# MoteWatch_Vers_2.net
KiCad netlist of a schematic drawn in EAGLE
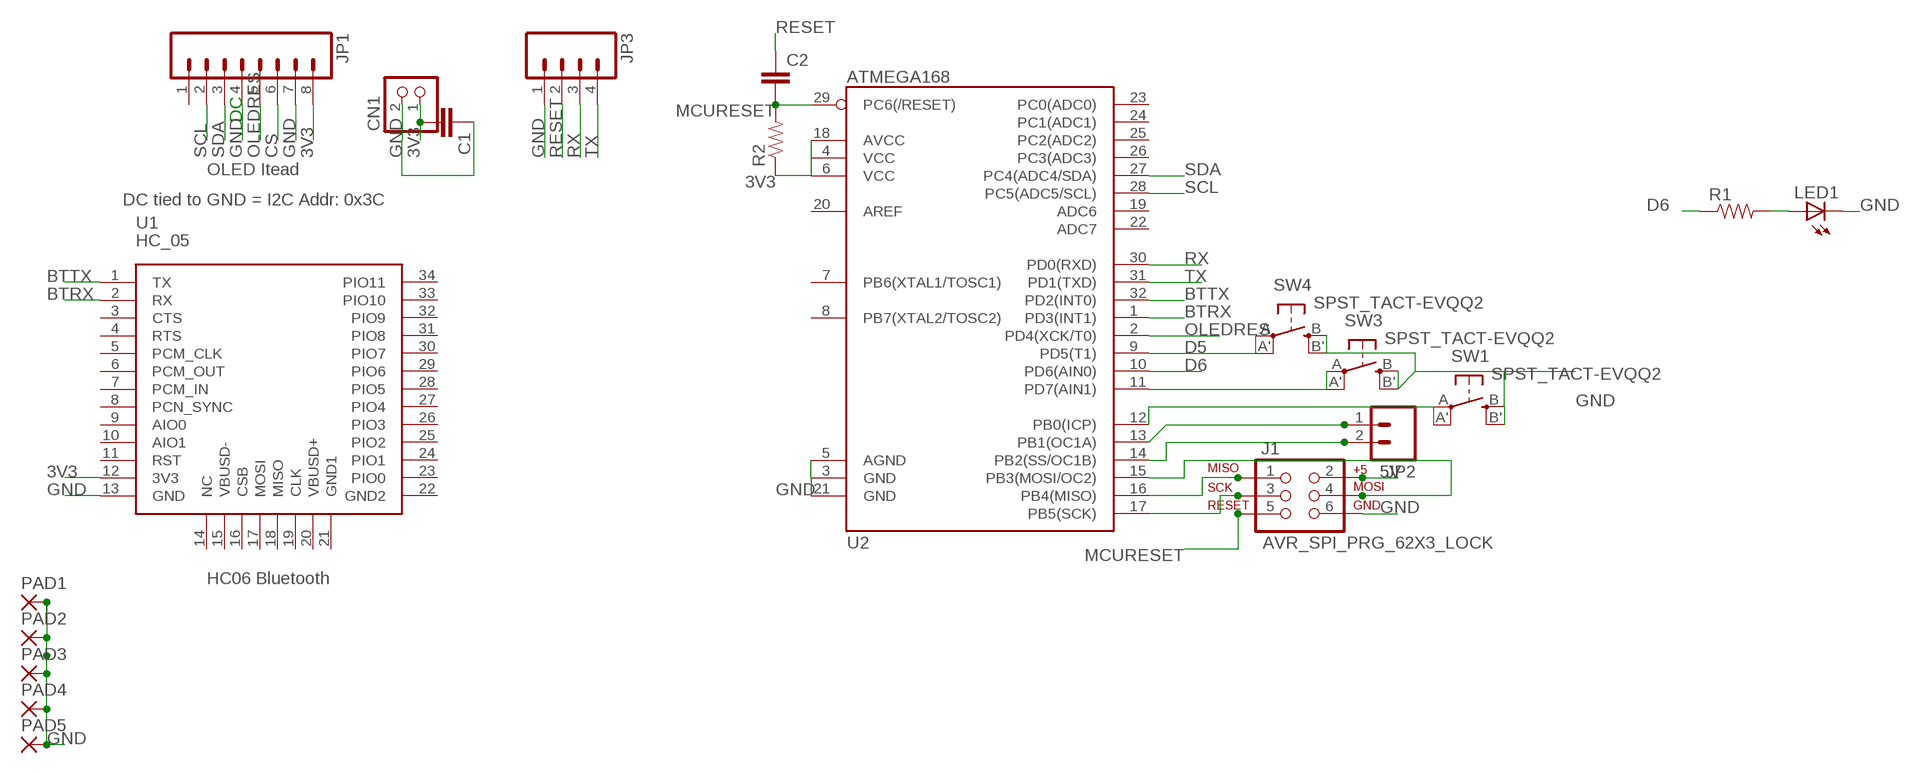
[diagram p0: schematic, sheet 1]

(export (version "E")
  (design (tool "Eeschema 10.0.6"))
  (components
    (comp (ref "C1")
      (value "CAP1206")
      (footprint "eagle-import:1206")
      (libsource (lib "eagle-import") (part "CAP1206"))
    )
    (comp (ref "C2")
      (value "CAP1206")
      (footprint "eagle-import:1206")
      (libsource (lib "eagle-import") (part "CAP1206"))
    )
    (comp (ref "CN1")
      (value "JST_2PIN-THM-RA")
      (footprint "eagle-import:JST-PH-2-THM-RA")
      (libsource (lib "eagle-import") (part "JST_2PIN-THM-RA"))
    )
    (comp (ref "J1")
      (value "AVR_SPI_PRG_62X3_LOCK")
      (footprint "eagle-import:2X3_LOCK")
      (libsource (lib "eagle-import") (part "AVR_SPI_PRG_62X3_LOCK"))
    )
    (comp (ref "JP1")
      (value "M08LOCK")
      (footprint "eagle-import:1X08_LOCK")
      (libsource (lib "eagle-import") (part "M08LOCK"))
    )
    (comp (ref "JP2")
      (value "M02LOCK")
      (footprint "eagle-import:1X02_LOCK")
      (libsource (lib "eagle-import") (part "M02LOCK"))
    )
    (comp (ref "JP3")
      (value "M04PTH")
      (footprint "eagle-import:1X04")
      (libsource (lib "eagle-import") (part "M04PTH"))
    )
    (comp (ref "LED1")
      (value "LED1206")
      (footprint "eagle-import:LED-1206")
      (libsource (lib "eagle-import") (part "LED1206"))
    )
    (comp (ref "PAD1")
      (value "SMD5")
      (footprint "eagle-import:SMD2,54-5,08")
      (libsource (lib "eagle-import") (part "SMD5"))
    )
    (comp (ref "PAD2")
      (value "SMD5")
      (footprint "eagle-import:SMD2,54-5,08")
      (libsource (lib "eagle-import") (part "SMD5"))
    )
    (comp (ref "PAD3")
      (value "SMD5")
      (footprint "eagle-import:SMD2,54-5,08")
      (libsource (lib "eagle-import") (part "SMD5"))
    )
    (comp (ref "PAD4")
      (value "SMD5")
      (footprint "eagle-import:SMD2,54-5,08")
      (libsource (lib "eagle-import") (part "SMD5"))
    )
    (comp (ref "PAD5")
      (value "SMD5")
      (footprint "eagle-import:SMD2,54-5,08")
      (libsource (lib "eagle-import") (part "SMD5"))
    )
    (comp (ref "R1")
      (value "RESISTOR1206")
      (footprint "eagle-import:1206")
      (libsource (lib "eagle-import") (part "RESISTOR1206"))
    )
    (comp (ref "R2")
      (value "RESISTOR1206")
      (footprint "eagle-import:1206")
      (libsource (lib "eagle-import") (part "RESISTOR1206"))
    )
    (comp (ref "SW1")
      (value "SPST_TACT-EVQQ2")
      (footprint "eagle-import:EVQ-Q2")
      (libsource (lib "eagle-import") (part "SPST_TACT-EVQQ2"))
    )
    (comp (ref "SW3")
      (value "SPST_TACT-EVQQ2")
      (footprint "eagle-import:EVQ-Q2")
      (libsource (lib "eagle-import") (part "SPST_TACT-EVQQ2"))
    )
    (comp (ref "SW4")
      (value "SPST_TACT-EVQQ2")
      (footprint "eagle-import:EVQ-Q2")
      (libsource (lib "eagle-import") (part "SPST_TACT-EVQQ2"))
    )
    (comp (ref "U1")
      (value "HC_05")
      (footprint "eagle-import:BLUETOOTH_SMD")
      (libsource (lib "eagle-import") (part "HC_05"))
    )
    (comp (ref "U2")
      (value "ATMEGA168")
      (footprint "eagle-import:TQFP32-08")
      (libsource (lib "eagle-import") (part "ATMEGA168"))
    )
  )
  (nets
    (net (code "1") (name "/3V3") (class "Default")
      (node (ref "C1") (pin "2") (pinfunction "2_2") (pintype "passive"))
      (node (ref "CN1") (pin "1") (pinfunction "2_1") (pintype "passive"))
      (node (ref "JP1") (pin "8") (pinfunction "8_8") (pintype "passive"))
      (node (ref "R2") (pin "1") (pinfunction "1_1") (pintype "passive"))
      (node (ref "U1") (pin "12") (pinfunction "3V3_12") (pintype "bidirectional"))
      (node (ref "U2") (pin "18") (pinfunction "AVCC_18") (pintype "bidirectional"))
      (node (ref "U2") (pin "4") (pinfunction "VCC_4") (pintype "bidirectional"))
      (node (ref "U2") (pin "6") (pinfunction "VCC_6") (pintype "bidirectional"))
    )
    (net (code "2") (name "/5V") (class "Default")
      (node (ref "J1") (pin "2") (pinfunction "2_2") (pintype "passive"))
    )
    (net (code "3") (name "/BTRX") (class "Default")
      (node (ref "U1") (pin "2") (pinfunction "RX_2") (pintype "bidirectional"))
      (node (ref "U2") (pin "1") (pinfunction "PD3(INT1)_1") (pintype "bidirectional"))
    )
    (net (code "4") (name "/BTTX") (class "Default")
      (node (ref "U1") (pin "1") (pinfunction "TX_1") (pintype "bidirectional"))
      (node (ref "U2") (pin "32") (pinfunction "PD2(INT0)_32") (pintype "bidirectional"))
    )
    (net (code "5") (name "/CS") (class "Default")
      (node (ref "JP1") (pin "6") (pinfunction "6_6") (pintype "passive"))
    )
    (net (code "6") (name "/D5") (class "Default")
      (node (ref "SW4") (pin "A") (pinfunction "P_A") (pintype "passive"))
      (node (ref "SW4") (pin "A'") (pinfunction "P1_A'") (pintype "passive"))
      (node (ref "U2") (pin "9") (pinfunction "PD5(T1)_9") (pintype "bidirectional"))
    )
    (net (code "7") (name "/D6") (class "Default")
      (node (ref "R1") (pin "1") (pinfunction "1_1") (pintype "passive"))
      (node (ref "U2") (pin "10") (pinfunction "PD6(AIN0)_10") (pintype "bidirectional"))
    )
    (net (code "8") (name "/GND") (class "Default")
      (node (ref "C1") (pin "1") (pinfunction "1_1") (pintype "passive"))
      (node (ref "CN1") (pin "2") (pinfunction "1_2") (pintype "passive"))
      (node (ref "J1") (pin "6") (pinfunction "6_6") (pintype "passive"))
      (node (ref "JP1") (pin "4") (pinfunction "4_4") (pintype "passive"))
      (node (ref "JP1") (pin "7") (pinfunction "7_7") (pintype "passive"))
      (node (ref "JP3") (pin "1") (pinfunction "1_1") (pintype "passive"))
      (node (ref "LED1") (pin "C") (pinfunction "C_C") (pintype "passive"))
      (node (ref "PAD1") (pin "1") (pinfunction "P_1") (pintype "passive"))
      (node (ref "PAD2") (pin "1") (pinfunction "P_1") (pintype "passive"))
      (node (ref "PAD3") (pin "1") (pinfunction "P_1") (pintype "passive"))
      (node (ref "PAD4") (pin "1") (pinfunction "P_1") (pintype "passive"))
      (node (ref "PAD5") (pin "1") (pinfunction "P_1") (pintype "passive"))
      (node (ref "SW1") (pin "B") (pinfunction "S_B") (pintype "passive"))
      (node (ref "SW1") (pin "B'") (pinfunction "S1_B'") (pintype "passive"))
      (node (ref "SW3") (pin "B") (pinfunction "S_B") (pintype "passive"))
      (node (ref "SW3") (pin "B'") (pinfunction "S1_B'") (pintype "passive"))
      (node (ref "SW4") (pin "B") (pinfunction "S_B") (pintype "passive"))
      (node (ref "SW4") (pin "B'") (pinfunction "S1_B'") (pintype "passive"))
      (node (ref "U1") (pin "13") (pinfunction "GND_13") (pintype "bidirectional"))
      (node (ref "U2") (pin "21") (pinfunction "GND_21") (pintype "bidirectional"))
      (node (ref "U2") (pin "3") (pinfunction "GND_3") (pintype "bidirectional"))
      (node (ref "U2") (pin "5") (pinfunction "AGND_5") (pintype "bidirectional"))
    )
    (net (code "9") (name "/MCURESET") (class "Default")
      (node (ref "C2") (pin "2") (pinfunction "2_2") (pintype "passive"))
      (node (ref "J1") (pin "5") (pinfunction "5_5") (pintype "passive"))
      (node (ref "R2") (pin "2") (pinfunction "2_2") (pintype "passive"))
      (node (ref "U2") (pin "29") (pinfunction "PC6(/RESET)_29") (pintype "bidirectional"))
    )
    (net (code "10") (name "/OLEDRES") (class "Default")
      (node (ref "JP1") (pin "5") (pinfunction "5_5") (pintype "passive"))
      (node (ref "U2") (pin "2") (pinfunction "PD4(XCK/T0)_2") (pintype "bidirectional"))
    )
    (net (code "11") (name "/RESET") (class "Default")
      (node (ref "C2") (pin "1") (pinfunction "1_1") (pintype "passive"))
      (node (ref "JP3") (pin "2") (pinfunction "2_2") (pintype "passive"))
    )
    (net (code "12") (name "/RX") (class "Default")
      (node (ref "JP3") (pin "3") (pinfunction "3_3") (pintype "passive"))
      (node (ref "U2") (pin "30") (pinfunction "PD0(RXD)_30") (pintype "bidirectional"))
    )
    (net (code "13") (name "/SCL") (class "Default")
      (node (ref "JP1") (pin "2") (pinfunction "2_2") (pintype "passive"))
      (node (ref "U2") (pin "28") (pinfunction "PC5(ADC5/SCL)_28") (pintype "bidirectional"))
    )
    (net (code "14") (name "/SDA") (class "Default")
      (node (ref "JP1") (pin "3") (pinfunction "3_3") (pintype "passive"))
      (node (ref "U2") (pin "27") (pinfunction "PC4(ADC4/SDA)_27") (pintype "bidirectional"))
    )
    (net (code "15") (name "/TX") (class "Default")
      (node (ref "JP3") (pin "4") (pinfunction "4_4") (pintype "passive"))
      (node (ref "U2") (pin "31") (pinfunction "PD1(TXD)_31") (pintype "bidirectional"))
    )
    (net (code "16") (name "Net-(LED1-PadA)") (class "Default")
      (node (ref "LED1") (pin "A") (pinfunction "A_A") (pintype "passive"))
      (node (ref "R1") (pin "2") (pinfunction "2_2") (pintype "passive"))
    )
    (net (code "17") (name "Net-(SW1-P)") (class "Default")
      (node (ref "SW1") (pin "A") (pinfunction "P_A") (pintype "passive"))
      (node (ref "SW1") (pin "A'") (pinfunction "P1_A'") (pintype "passive"))
      (node (ref "U2") (pin "12") (pinfunction "PB0(ICP)_12") (pintype "bidirectional"))
    )
    (net (code "18") (name "Net-(SW3-P)") (class "Default")
      (node (ref "SW3") (pin "A") (pinfunction "P_A") (pintype "passive"))
      (node (ref "SW3") (pin "A'") (pinfunction "P1_A'") (pintype "passive"))
      (node (ref "U2") (pin "11") (pinfunction "PD7(AIN1)_11") (pintype "bidirectional"))
    )
    (net (code "19") (name "Net-(U2-PB1(OC1A))") (class "Default")
      (node (ref "JP2") (pin "1") (pinfunction "1_1") (pintype "passive"))
      (node (ref "U2") (pin "13") (pinfunction "PB1(OC1A)_13") (pintype "bidirectional"))
    )
    (net (code "20") (name "Net-(U2-PB2(SS{slash}OC1B))") (class "Default")
      (node (ref "JP2") (pin "2") (pinfunction "2_2") (pintype "passive"))
      (node (ref "U2") (pin "14") (pinfunction "PB2(SS/OC1B)_14") (pintype "bidirectional"))
    )
    (net (code "21") (name "Net-(U2-PB3(MOSI{slash}OC2))") (class "Default")
      (node (ref "J1") (pin "4") (pinfunction "4_4") (pintype "passive"))
      (node (ref "U2") (pin "15") (pinfunction "PB3(MOSI/OC2)_15") (pintype "bidirectional"))
    )
    (net (code "22") (name "Net-(U2-PB4(MISO))") (class "Default")
      (node (ref "J1") (pin "1") (pinfunction "1_1") (pintype "passive"))
      (node (ref "U2") (pin "16") (pinfunction "PB4(MISO)_16") (pintype "bidirectional"))
    )
    (net (code "23") (name "Net-(U2-PB5(SCK))") (class "Default")
      (node (ref "J1") (pin "3") (pinfunction "3_3") (pintype "passive"))
      (node (ref "U2") (pin "17") (pinfunction "PB5(SCK)_17") (pintype "bidirectional"))
    )
    (net (code "24") (name "unconnected-(JP1-Pad1)") (class "Default")
      (node (ref "JP1") (pin "1") (pinfunction "1_1") (pintype "passive"))
    )
    (net (code "25") (name "unconnected-(U1-AIO0-Pad9)") (class "Default")
      (node (ref "U1") (pin "9") (pinfunction "AIO0_9") (pintype "bidirectional"))
    )
    (net (code "26") (name "unconnected-(U1-AIO1-Pad10)") (class "Default")
      (node (ref "U1") (pin "10") (pinfunction "AIO1_10") (pintype "bidirectional"))
    )
    (net (code "27") (name "unconnected-(U1-CLK-Pad19)") (class "Default")
      (node (ref "U1") (pin "19") (pinfunction "CLK_19") (pintype "bidirectional"))
    )
    (net (code "28") (name "unconnected-(U1-CSB-Pad16)") (class "Default")
      (node (ref "U1") (pin "16") (pinfunction "CSB_16") (pintype "bidirectional"))
    )
    (net (code "29") (name "unconnected-(U1-CTS-Pad3)") (class "Default")
      (node (ref "U1") (pin "3") (pinfunction "CTS_3") (pintype "bidirectional"))
    )
    (net (code "30") (name "unconnected-(U1-GND1-Pad21)") (class "Default")
      (node (ref "U1") (pin "21") (pinfunction "GND1_21") (pintype "bidirectional"))
    )
    (net (code "31") (name "unconnected-(U1-GND2-Pad22)") (class "Default")
      (node (ref "U1") (pin "22") (pinfunction "GND2_22") (pintype "bidirectional"))
    )
    (net (code "32") (name "unconnected-(U1-MISO-Pad18)") (class "Default")
      (node (ref "U1") (pin "18") (pinfunction "MISO_18") (pintype "bidirectional"))
    )
    (net (code "33") (name "unconnected-(U1-MOSI-Pad17)") (class "Default")
      (node (ref "U1") (pin "17") (pinfunction "MOSI_17") (pintype "bidirectional"))
    )
    (net (code "34") (name "unconnected-(U1-NC-Pad14)") (class "Default")
      (node (ref "U1") (pin "14") (pinfunction "NC_14") (pintype "bidirectional"))
    )
    (net (code "35") (name "unconnected-(U1-PCM_CLK-Pad5)") (class "Default")
      (node (ref "U1") (pin "5") (pinfunction "PCM_CLK_5") (pintype "bidirectional"))
    )
    (net (code "36") (name "unconnected-(U1-PCM_IN-Pad7)") (class "Default")
      (node (ref "U1") (pin "7") (pinfunction "PCM_IN_7") (pintype "bidirectional"))
    )
    (net (code "37") (name "unconnected-(U1-PCM_OUT-Pad6)") (class "Default")
      (node (ref "U1") (pin "6") (pinfunction "PCM_OUT_6") (pintype "bidirectional"))
    )
    (net (code "38") (name "unconnected-(U1-PCN_SYNC-Pad8)") (class "Default")
      (node (ref "U1") (pin "8") (pinfunction "PCN_SYNC_8") (pintype "bidirectional"))
    )
    (net (code "39") (name "unconnected-(U1-PIO0-Pad23)") (class "Default")
      (node (ref "U1") (pin "23") (pinfunction "PIO0_23") (pintype "bidirectional"))
    )
    (net (code "40") (name "unconnected-(U1-PIO1-Pad24)") (class "Default")
      (node (ref "U1") (pin "24") (pinfunction "PIO1_24") (pintype "bidirectional"))
    )
    (net (code "41") (name "unconnected-(U1-PIO2-Pad25)") (class "Default")
      (node (ref "U1") (pin "25") (pinfunction "PIO2_25") (pintype "bidirectional"))
    )
    (net (code "42") (name "unconnected-(U1-PIO3-Pad26)") (class "Default")
      (node (ref "U1") (pin "26") (pinfunction "PIO3_26") (pintype "bidirectional"))
    )
    (net (code "43") (name "unconnected-(U1-PIO4-Pad27)") (class "Default")
      (node (ref "U1") (pin "27") (pinfunction "PIO4_27") (pintype "bidirectional"))
    )
    (net (code "44") (name "unconnected-(U1-PIO5-Pad28)") (class "Default")
      (node (ref "U1") (pin "28") (pinfunction "PIO5_28") (pintype "bidirectional"))
    )
    (net (code "45") (name "unconnected-(U1-PIO6-Pad29)") (class "Default")
      (node (ref "U1") (pin "29") (pinfunction "PIO6_29") (pintype "bidirectional"))
    )
    (net (code "46") (name "unconnected-(U1-PIO7-Pad30)") (class "Default")
      (node (ref "U1") (pin "30") (pinfunction "PIO7_30") (pintype "bidirectional"))
    )
    (net (code "47") (name "unconnected-(U1-PIO8-Pad31)") (class "Default")
      (node (ref "U1") (pin "31") (pinfunction "PIO8_31") (pintype "bidirectional"))
    )
    (net (code "48") (name "unconnected-(U1-PIO9-Pad32)") (class "Default")
      (node (ref "U1") (pin "32") (pinfunction "PIO9_32") (pintype "bidirectional"))
    )
    (net (code "49") (name "unconnected-(U1-PIO10-Pad33)") (class "Default")
      (node (ref "U1") (pin "33") (pinfunction "PIO10_33") (pintype "bidirectional"))
    )
    (net (code "50") (name "unconnected-(U1-PIO11-Pad34)") (class "Default")
      (node (ref "U1") (pin "34") (pinfunction "PIO11_34") (pintype "bidirectional"))
    )
    (net (code "51") (name "unconnected-(U1-RST-Pad11)") (class "Default")
      (node (ref "U1") (pin "11") (pinfunction "RST_11") (pintype "bidirectional"))
    )
    (net (code "52") (name "unconnected-(U1-RTS-Pad4)") (class "Default")
      (node (ref "U1") (pin "4") (pinfunction "RTS_4") (pintype "bidirectional"))
    )
    (net (code "53") (name "unconnected-(U1-VBUSD+-Pad20)") (class "Default")
      (node (ref "U1") (pin "20") (pinfunction "VBUSD+_20") (pintype "bidirectional"))
    )
    (net (code "54") (name "unconnected-(U1-VBUSD--Pad15)") (class "Default")
      (node (ref "U1") (pin "15") (pinfunction "VBUSD-_15") (pintype "bidirectional"))
    )
    (net (code "55") (name "unconnected-(U2-ADC6-Pad19)") (class "Default")
      (node (ref "U2") (pin "19") (pinfunction "ADC6_19") (pintype "bidirectional"))
    )
    (net (code "56") (name "unconnected-(U2-ADC7-Pad22)") (class "Default")
      (node (ref "U2") (pin "22") (pinfunction "ADC7_22") (pintype "bidirectional"))
    )
    (net (code "57") (name "unconnected-(U2-AREF-Pad20)") (class "Default")
      (node (ref "U2") (pin "20") (pinfunction "AREF_20") (pintype "bidirectional"))
    )
    (net (code "58") (name "unconnected-(U2-PB6(XTAL1{slash}TOSC1)-Pad7)") (class "Default")
      (node (ref "U2") (pin "7") (pinfunction "PB6(XTAL1/TOSC1)_7") (pintype "bidirectional"))
    )
    (net (code "59") (name "unconnected-(U2-PB7(XTAL2{slash}TOSC2)-Pad8)") (class "Default")
      (node (ref "U2") (pin "8") (pinfunction "PB7(XTAL2/TOSC2)_8") (pintype "bidirectional"))
    )
    (net (code "60") (name "unconnected-(U2-PC0(ADC0)-Pad23)") (class "Default")
      (node (ref "U2") (pin "23") (pinfunction "PC0(ADC0)_23") (pintype "bidirectional"))
    )
    (net (code "61") (name "unconnected-(U2-PC1(ADC1)-Pad24)") (class "Default")
      (node (ref "U2") (pin "24") (pinfunction "PC1(ADC1)_24") (pintype "bidirectional"))
    )
    (net (code "62") (name "unconnected-(U2-PC2(ADC2)-Pad25)") (class "Default")
      (node (ref "U2") (pin "25") (pinfunction "PC2(ADC2)_25") (pintype "bidirectional"))
    )
    (net (code "63") (name "unconnected-(U2-PC3(ADC3)-Pad26)") (class "Default")
      (node (ref "U2") (pin "26") (pinfunction "PC3(ADC3)_26") (pintype "bidirectional"))
    )
  )
)
